# ground_detector.net
KiCad netlist of a schematic drawn in Altium Designer
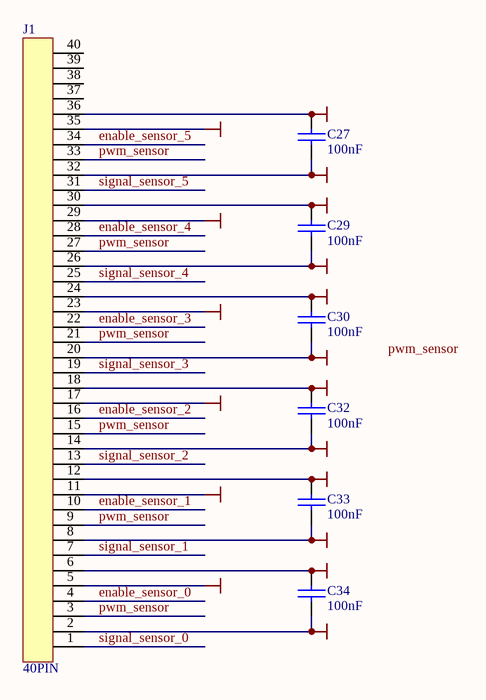
[diagram p0: ground_detector.SchDoc]

(export (version "E")
  (design (tool "Eeschema 10.0.6"))
  (components
    (comp (ref "C27") (value "100nF") (footprint "TCONDO") (libsource (lib "prop2009") (part "TCONDO")))
    (comp (ref "C29") (value "100nF") (footprint "TCONDO") (libsource (lib "prop2009") (part "TCONDO")))
    (comp (ref "C30") (value "100nF") (footprint "TCONDO") (libsource (lib "prop2009") (part "TCONDO")))
    (comp (ref "C32") (value "100nF") (footprint "TCONDO") (libsource (lib "prop2009") (part "TCONDO")))
    (comp (ref "C33") (value "100nF") (footprint "TCONDO") (libsource (lib "prop2009") (part "TCONDO")))
    (comp (ref "C34") (value "100nF") (footprint "TCONDO") (libsource (lib "prop2009") (part "TCONDO")))
    (comp (ref "J1") (value "40PIN") (footprint "HE10-40V") (libsource (lib "prop2009") (part "40PIN")))
  )
  (nets
    (net (code "1") (name "/enable_sensor_0") (class "Default")
      (node (ref "J1") (pin "4") (pinfunction "4_4") (pintype "passive"))
    )
    (net (code "2") (name "/enable_sensor_1") (class "Default")
      (node (ref "J1") (pin "10") (pinfunction "10_10") (pintype "passive"))
    )
    (net (code "3") (name "/enable_sensor_2") (class "Default")
      (node (ref "J1") (pin "16") (pinfunction "16_16") (pintype "passive"))
    )
    (net (code "4") (name "/enable_sensor_3") (class "Default")
      (node (ref "J1") (pin "22") (pinfunction "22_22") (pintype "passive"))
    )
    (net (code "5") (name "/enable_sensor_4") (class "Default")
      (node (ref "J1") (pin "28") (pinfunction "28_28") (pintype "passive"))
    )
    (net (code "6") (name "/enable_sensor_5") (class "Default")
      (node (ref "J1") (pin "34") (pinfunction "34_34") (pintype "passive"))
    )
    (net (code "7") (name "/pwm_sensor") (class "Default")
      (node (ref "J1") (pin "15") (pinfunction "15_15") (pintype "passive"))
      (node (ref "J1") (pin "21") (pinfunction "21_21") (pintype "passive"))
      (node (ref "J1") (pin "27") (pinfunction "27_27") (pintype "passive"))
      (node (ref "J1") (pin "3") (pinfunction "3_3") (pintype "passive"))
      (node (ref "J1") (pin "33") (pinfunction "33_33") (pintype "passive"))
      (node (ref "J1") (pin "9") (pinfunction "9_9") (pintype "passive"))
    )
    (net (code "8") (name "/signal_sensor_0") (class "Default")
      (node (ref "J1") (pin "1") (pinfunction "1_1") (pintype "passive"))
    )
    (net (code "9") (name "/signal_sensor_1") (class "Default")
      (node (ref "J1") (pin "7") (pinfunction "7_7") (pintype "passive"))
    )
    (net (code "10") (name "/signal_sensor_2") (class "Default")
      (node (ref "J1") (pin "13") (pinfunction "13_13") (pintype "passive"))
    )
    (net (code "11") (name "/signal_sensor_3") (class "Default")
      (node (ref "J1") (pin "19") (pinfunction "19_19") (pintype "passive"))
    )
    (net (code "12") (name "/signal_sensor_4") (class "Default")
      (node (ref "J1") (pin "25") (pinfunction "25_25") (pintype "passive"))
    )
    (net (code "13") (name "/signal_sensor_5") (class "Default")
      (node (ref "J1") (pin "31") (pinfunction "31_31") (pintype "passive"))
    )
    (net (code "14") (name "3V3") (class "Default")
      (node (ref "C27") (pin "1") (pintype "passive"))
      (node (ref "C29") (pin "1") (pintype "passive"))
      (node (ref "C30") (pin "1") (pintype "passive"))
      (node (ref "C32") (pin "1") (pintype "passive"))
      (node (ref "C33") (pin "1") (pintype "passive"))
      (node (ref "C34") (pin "1") (pintype "passive"))
      (node (ref "J1") (pin "12") (pinfunction "12_12") (pintype "passive"))
      (node (ref "J1") (pin "18") (pinfunction "18_18") (pintype "passive"))
      (node (ref "J1") (pin "24") (pinfunction "24_24") (pintype "passive"))
      (node (ref "J1") (pin "30") (pinfunction "30_30") (pintype "passive"))
      (node (ref "J1") (pin "36") (pinfunction "36_36") (pintype "passive"))
      (node (ref "J1") (pin "6") (pinfunction "6_6") (pintype "passive"))
    )
    (net (code "15") (name "GND") (class "Default")
      (node (ref "C27") (pin "2") (pintype "passive"))
      (node (ref "C29") (pin "2") (pintype "passive"))
      (node (ref "C30") (pin "2") (pintype "passive"))
      (node (ref "C32") (pin "2") (pintype "passive"))
      (node (ref "C33") (pin "2") (pintype "passive"))
      (node (ref "C34") (pin "2") (pintype "passive"))
      (node (ref "J1") (pin "11") (pinfunction "11_11") (pintype "passive"))
      (node (ref "J1") (pin "14") (pinfunction "14_14") (pintype "passive"))
      (node (ref "J1") (pin "17") (pinfunction "17_17") (pintype "passive"))
      (node (ref "J1") (pin "2") (pinfunction "2_2") (pintype "passive"))
      (node (ref "J1") (pin "20") (pinfunction "20_20") (pintype "passive"))
      (node (ref "J1") (pin "23") (pinfunction "23_23") (pintype "passive"))
      (node (ref "J1") (pin "26") (pinfunction "26_26") (pintype "passive"))
      (node (ref "J1") (pin "29") (pinfunction "29_29") (pintype "passive"))
      (node (ref "J1") (pin "32") (pinfunction "32_32") (pintype "passive"))
      (node (ref "J1") (pin "35") (pinfunction "35_35") (pintype "passive"))
      (node (ref "J1") (pin "5") (pinfunction "5_5") (pintype "passive"))
      (node (ref "J1") (pin "8") (pinfunction "8_8") (pintype "passive"))
    )
    (net (code "16") (name "unconnected-(J1-Pad37)") (class "Default")
      (node (ref "J1") (pin "37") (pinfunction "37_37") (pintype "passive"))
    )
    (net (code "17") (name "unconnected-(J1-Pad38)") (class "Default")
      (node (ref "J1") (pin "38") (pinfunction "38_38") (pintype "passive"))
    )
    (net (code "18") (name "unconnected-(J1-Pad39)") (class "Default")
      (node (ref "J1") (pin "39") (pinfunction "39_39") (pintype "passive"))
    )
    (net (code "19") (name "unconnected-(J1-Pad40)") (class "Default")
      (node (ref "J1") (pin "40") (pinfunction "40_40") (pintype "passive"))
    )
  )
)
